# Main.net
KiCad netlist of a schematic drawn in Altium Designer
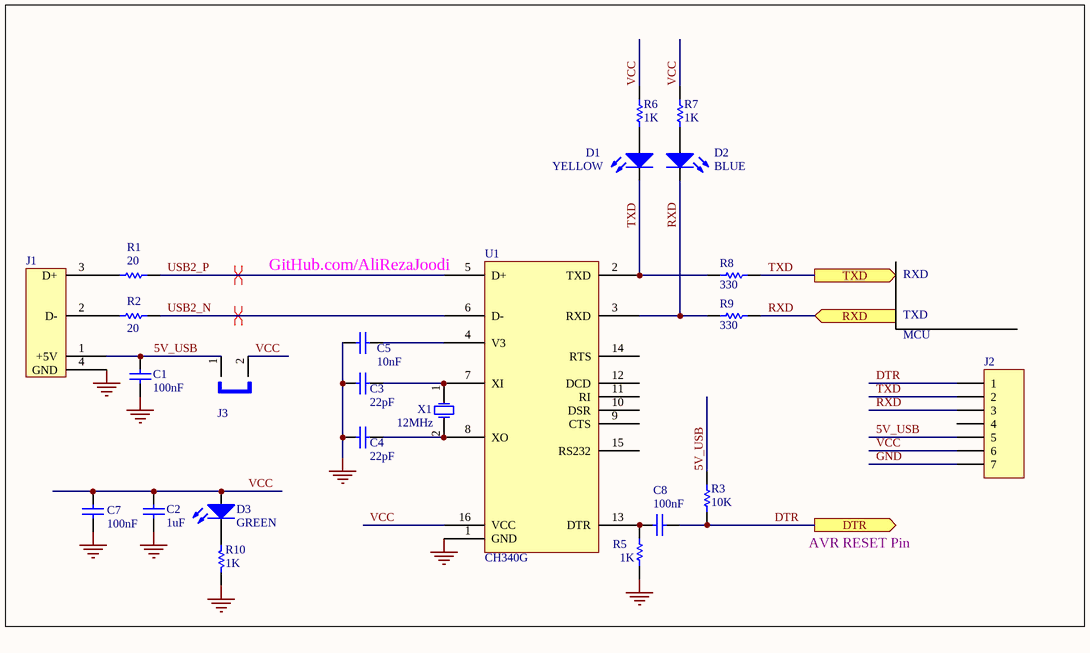
[diagram p0: Main.SchDoc]

(export (version "E")
  (design (tool "Eeschema 10.0.6"))
  (components
    (comp (ref "C1")
      (value "100nF")
      (footprint "0805")
      (description "Capacitor")
      (fields (field (name "MANUFACTURER") "Generic Components") (field (name "PUBLISHER") "Altium Limited"))
      (libsource (lib "Miscellaneous Devices") (part "Cap"))
    )
    (comp (ref "C2")
      (value "1uF")
      (footprint "0805")
      (description "Capacitor")
      (fields (field (name "MANUFACTURER") "Generic Components") (field (name "PUBLISHER") "Altium Limited"))
      (libsource (lib "Miscellaneous Devices") (part "Cap"))
    )
    (comp (ref "C3")
      (value "22pF")
      (footprint "0805")
      (description "Capacitor")
      (fields (field (name "MANUFACTURER") "Generic Components") (field (name "PUBLISHER") "Altium Limited"))
      (libsource (lib "Miscellaneous Devices") (part "Cap"))
    )
    (comp (ref "C4")
      (value "22pF")
      (footprint "0805")
      (description "Capacitor")
      (fields (field (name "MANUFACTURER") "Generic Components") (field (name "PUBLISHER") "Altium Limited"))
      (libsource (lib "Miscellaneous Devices") (part "Cap"))
    )
    (comp (ref "C5")
      (value "10nF")
      (footprint "0805")
      (description "Capacitor")
      (fields (field (name "MANUFACTURER") "Generic Components") (field (name "PUBLISHER") "Altium Limited"))
      (libsource (lib "Miscellaneous Devices") (part "Cap"))
    )
    (comp (ref "C7")
      (value "100nF")
      (footprint "0805")
      (description "Capacitor")
      (fields (field (name "MANUFACTURER") "Generic Components") (field (name "PUBLISHER") "Altium Limited"))
      (libsource (lib "Miscellaneous Devices") (part "Cap"))
    )
    (comp (ref "C8")
      (value "100nF")
      (footprint "0805")
      (description "Capacitor")
      (fields (field (name "MANUFACTURER") "Generic Components") (field (name "PUBLISHER") "Altium Limited"))
      (libsource (lib "Miscellaneous Devices") (part "Cap"))
    )
    (comp (ref "D1")
      (value "YELLOW")
      (footprint "0805_Diode")
      (description "Typical INFRARED GaAs LED")
      (fields (field (name "MANUFACTURER") "Generic Components") (field (name "PUBLISHER") "Altium Limited"))
      (libsource (lib "my Libraries") (part "Optical Transmitter"))
    )
    (comp (ref "D2")
      (value "BLUE")
      (footprint "0805_Diode")
      (description "Typical INFRARED GaAs LED")
      (fields (field (name "MANUFACTURER") "Generic Components") (field (name "PUBLISHER") "Altium Limited"))
      (libsource (lib "my Libraries") (part "Optical Transmitter"))
    )
    (comp (ref "D3")
      (value "GREEN")
      (footprint "0805_Diode")
      (description "Typical INFRARED GaAs LED")
      (fields (field (name "MANUFACTURER") "Generic Components") (field (name "PUBLISHER") "Altium Limited"))
      (libsource (lib "my Libraries") (part "Optical Transmitter"))
    )
    (comp (ref "J1")
      (value "USB Connector")
      (footprint "USB2.5-2H4D")
      (libsource (lib "my Libraries") (part "CONNECTOR_USB"))
    )
    (comp (ref "J2")
      (value "7PIN")
      (footprint "HDR1X7")
      (description "Header, 7-Pin")
      (fields (field (name "MANUFACTURER") "Generic Components") (field (name "PUBLISHER") "Altium Limited"))
      (libsource (lib "Miscellaneous Connectors") (part "Header 7"))
    )
    (comp (ref "J3")
      (value "Jumper 2pin")
      (footprint "Jumper_Solder_2Pad_100X60")
      (description "Jumper")
      (fields (field (name "MANUFACTURER") "Generic Components") (field (name "PUBLISHER") "Altium Limited"))
      (libsource (lib "Connector") (part "Jumper 2pin"))
    )
    (comp (ref "R1")
      (value "20")
      (footprint "0805")
      (description "Resistor")
      (fields (field (name "PUBLISHER") "Altium Limited"))
      (libsource (lib "Miscellaneous Devices") (part "Res1"))
    )
    (comp (ref "R2")
      (value "20")
      (footprint "0805")
      (description "Resistor")
      (fields (field (name "PUBLISHER") "Altium Limited"))
      (libsource (lib "Miscellaneous Devices") (part "Res1"))
    )
    (comp (ref "R3")
      (value "10K")
      (footprint "0805")
      (description "Resistor")
      (fields (field (name "PUBLISHER") "Altium Limited"))
      (libsource (lib "Miscellaneous Devices") (part "Res1"))
    )
    (comp (ref "R5")
      (value "1K")
      (footprint "0805")
      (description "Resistor")
      (fields (field (name "PUBLISHER") "Altium Limited"))
      (libsource (lib "Miscellaneous Devices") (part "Res1"))
    )
    (comp (ref "R6")
      (value "1K")
      (footprint "0805")
      (description "Resistor")
      (fields (field (name "PUBLISHER") "Altium Limited"))
      (libsource (lib "Miscellaneous Devices") (part "Res1"))
    )
    (comp (ref "R7")
      (value "1K")
      (footprint "0805")
      (description "Resistor")
      (fields (field (name "PUBLISHER") "Altium Limited"))
      (libsource (lib "Miscellaneous Devices") (part "Res1"))
    )
    (comp (ref "R8")
      (value "330")
      (footprint "0805")
      (description "Resistor")
      (fields (field (name "PUBLISHER") "Altium Limited"))
      (libsource (lib "Miscellaneous Devices") (part "Res1"))
    )
    (comp (ref "R9")
      (value "330")
      (footprint "0805")
      (description "Resistor")
      (fields (field (name "PUBLISHER") "Altium Limited"))
      (libsource (lib "Miscellaneous Devices") (part "Res1"))
    )
    (comp (ref "R10")
      (value "1K")
      (footprint "0805")
      (description "Resistor")
      (fields (field (name "PUBLISHER") "Altium Limited"))
      (libsource (lib "Miscellaneous Devices") (part "Res1"))
    )
    (comp (ref "U1")
      (value "CH340G")
      (footprint "SOIC127P602-16BM")
      (description "USB to UART Interface")
      (libsource (lib "my Libraries") (part "CH340G"))
    )
    (comp (ref "X1")
      (value "12MHz")
      (footprint "HC49/4H_SMX")
      (description "Crystal Oscillator")
      (fields (field (name "MANUFACTURER") "Generic Components") (field (name "PUBLISHER") "Altium Limited"))
      (libsource (lib "Miscellaneous Devices") (part "XTAL"))
    )
  )
  (nets
    (net (code "1") (name "/5V_USB") (class "Default")
      (node (ref "C1") (pin "2") (pinfunction "2_2") (pintype "passive"))
      (node (ref "J1") (pin "1") (pinfunction "+5V_1") (pintype "passive"))
      (node (ref "J2") (pin "5") (pinfunction "5_5") (pintype "passive"))
      (node (ref "J3") (pin "1") (pinfunction "1_1") (pintype "passive"))
      (node (ref "R3") (pin "2") (pinfunction "2_2") (pintype "passive"))
    )
    (net (code "2") (name "/DTR") (class "Default")
      (node (ref "C8") (pin "1") (pinfunction "1_1") (pintype "passive"))
      (node (ref "J2") (pin "1") (pinfunction "1_1") (pintype "passive"))
      (node (ref "R3") (pin "1") (pinfunction "1_1") (pintype "passive"))
    )
    (net (code "3") (name "/RXD") (class "Default")
      (node (ref "D2") (pin "2") (pinfunction "K_2") (pintype "passive"))
      (node (ref "J2") (pin "3") (pinfunction "3_3") (pintype "passive"))
      (node (ref "R9") (pin "1") (pinfunction "1_1") (pintype "passive"))
      (node (ref "R9") (pin "2") (pinfunction "2_2") (pintype "passive"))
      (node (ref "U1") (pin "3") (pinfunction "RXD_3") (pintype "passive"))
    )
    (net (code "4") (name "/TXD") (class "Default")
      (node (ref "D1") (pin "2") (pinfunction "K_2") (pintype "passive"))
      (node (ref "J2") (pin "2") (pinfunction "2_2") (pintype "passive"))
      (node (ref "R8") (pin "1") (pinfunction "1_1") (pintype "passive"))
      (node (ref "R8") (pin "2") (pinfunction "2_2") (pintype "passive"))
      (node (ref "U1") (pin "2") (pinfunction "TXD_2") (pintype "passive"))
    )
    (net (code "5") (name "/USB2_N") (class "Default")
      (node (ref "R2") (pin "1") (pinfunction "1_1") (pintype "passive"))
      (node (ref "U1") (pin "6") (pinfunction "D-_6") (pintype "passive"))
    )
    (net (code "6") (name "/USB2_P") (class "Default")
      (node (ref "R1") (pin "1") (pinfunction "1_1") (pintype "passive"))
      (node (ref "U1") (pin "5") (pinfunction "D+_5") (pintype "passive"))
    )
    (net (code "7") (name "/VCC") (class "Default")
      (node (ref "C2") (pin "2") (pinfunction "2_2") (pintype "passive"))
      (node (ref "C7") (pin "2") (pinfunction "2_2") (pintype "passive"))
      (node (ref "D3") (pin "1") (pinfunction "A_1") (pintype "passive"))
      (node (ref "J2") (pin "6") (pinfunction "6_6") (pintype "passive"))
      (node (ref "J3") (pin "2") (pinfunction "2_2") (pintype "passive"))
      (node (ref "R6") (pin "1") (pinfunction "1_1") (pintype "passive"))
      (node (ref "R7") (pin "1") (pinfunction "1_1") (pintype "passive"))
      (node (ref "U1") (pin "16") (pinfunction "VCC_16") (pintype "power_in"))
    )
    (net (code "8") (name "GND") (class "Default")
      (node (ref "C1") (pin "1") (pinfunction "1_1") (pintype "passive"))
      (node (ref "C2") (pin "1") (pinfunction "1_1") (pintype "passive"))
      (node (ref "C3") (pin "2") (pinfunction "2_2") (pintype "passive"))
      (node (ref "C4") (pin "2") (pinfunction "2_2") (pintype "passive"))
      (node (ref "C5") (pin "2") (pinfunction "2_2") (pintype "passive"))
      (node (ref "C7") (pin "1") (pinfunction "1_1") (pintype "passive"))
      (node (ref "J1") (pin "4") (pinfunction "GND_4") (pintype "passive"))
      (node (ref "J2") (pin "7") (pinfunction "7_7") (pintype "passive"))
      (node (ref "R10") (pin "2") (pinfunction "2_2") (pintype "passive"))
      (node (ref "R5") (pin "1") (pinfunction "1_1") (pintype "passive"))
      (node (ref "U1") (pin "1") (pinfunction "GND_1") (pintype "power_in"))
    )
    (net (code "9") (name "Net-(D1-A)") (class "Default")
      (node (ref "D1") (pin "1") (pinfunction "A_1") (pintype "passive"))
      (node (ref "R6") (pin "2") (pinfunction "2_2") (pintype "passive"))
    )
    (net (code "10") (name "Net-(D2-A)") (class "Default")
      (node (ref "D2") (pin "1") (pinfunction "A_1") (pintype "passive"))
      (node (ref "R7") (pin "2") (pinfunction "2_2") (pintype "passive"))
    )
    (net (code "11") (name "Net-(D3-K)") (class "Default")
      (node (ref "D3") (pin "2") (pinfunction "K_2") (pintype "passive"))
      (node (ref "R10") (pin "1") (pinfunction "1_1") (pintype "passive"))
    )
    (net (code "12") (name "Net-(J1-D+)") (class "Default")
      (node (ref "J1") (pin "3") (pinfunction "D+_3") (pintype "passive"))
      (node (ref "R1") (pin "2") (pinfunction "2_2") (pintype "passive"))
    )
    (net (code "13") (name "Net-(J1-D-)") (class "Default")
      (node (ref "J1") (pin "2") (pinfunction "D-_2") (pintype "passive"))
      (node (ref "R2") (pin "2") (pinfunction "2_2") (pintype "passive"))
    )
    (net (code "14") (name "Net-(U1-DTR)") (class "Default")
      (node (ref "C8") (pin "2") (pinfunction "2_2") (pintype "passive"))
      (node (ref "R5") (pin "2") (pinfunction "2_2") (pintype "passive"))
      (node (ref "U1") (pin "13") (pinfunction "DTR_13") (pintype "passive"))
    )
    (net (code "15") (name "Net-(U1-V3)") (class "Default")
      (node (ref "C5") (pin "1") (pinfunction "1_1") (pintype "passive"))
      (node (ref "U1") (pin "4") (pinfunction "V3_4") (pintype "power_in"))
    )
    (net (code "16") (name "Net-(U1-XI)") (class "Default")
      (node (ref "C3") (pin "1") (pinfunction "1_1") (pintype "passive"))
      (node (ref "U1") (pin "7") (pinfunction "XI_7") (pintype "passive"))
      (node (ref "X1") (pin "1") (pinfunction "OSC1_1") (pintype "passive"))
    )
    (net (code "17") (name "Net-(U1-XO)") (class "Default")
      (node (ref "C4") (pin "1") (pinfunction "1_1") (pintype "passive"))
      (node (ref "U1") (pin "8") (pinfunction "XO_8") (pintype "passive"))
      (node (ref "X1") (pin "2") (pinfunction "OSC2_2") (pintype "passive"))
    )
    (net (code "18") (name "unconnected-(J2-Pad4)") (class "Default")
      (node (ref "J2") (pin "4") (pinfunction "4_4") (pintype "passive"))
    )
    (net (code "19") (name "unconnected-(U1-CTS-Pad9)") (class "Default")
      (node (ref "U1") (pin "9") (pinfunction "CTS_9") (pintype "passive"))
    )
    (net (code "20") (name "unconnected-(U1-DCD-Pad12)") (class "Default")
      (node (ref "U1") (pin "12") (pinfunction "DCD_12") (pintype "passive"))
    )
    (net (code "21") (name "unconnected-(U1-DSR-Pad10)") (class "Default")
      (node (ref "U1") (pin "10") (pinfunction "DSR_10") (pintype "passive"))
    )
    (net (code "22") (name "unconnected-(U1-RI-Pad11)") (class "Default")
      (node (ref "U1") (pin "11") (pinfunction "RI_11") (pintype "passive"))
    )
    (net (code "23") (name "unconnected-(U1-RS232-Pad15)") (class "Default")
      (node (ref "U1") (pin "15") (pinfunction "RS232_15") (pintype "passive"))
    )
    (net (code "24") (name "unconnected-(U1-RTS-Pad14)") (class "Default")
      (node (ref "U1") (pin "14") (pinfunction "RTS_14") (pintype "passive"))
    )
  )
)
